# untitled.net
KiCad netlist of a schematic drawn in EAGLE
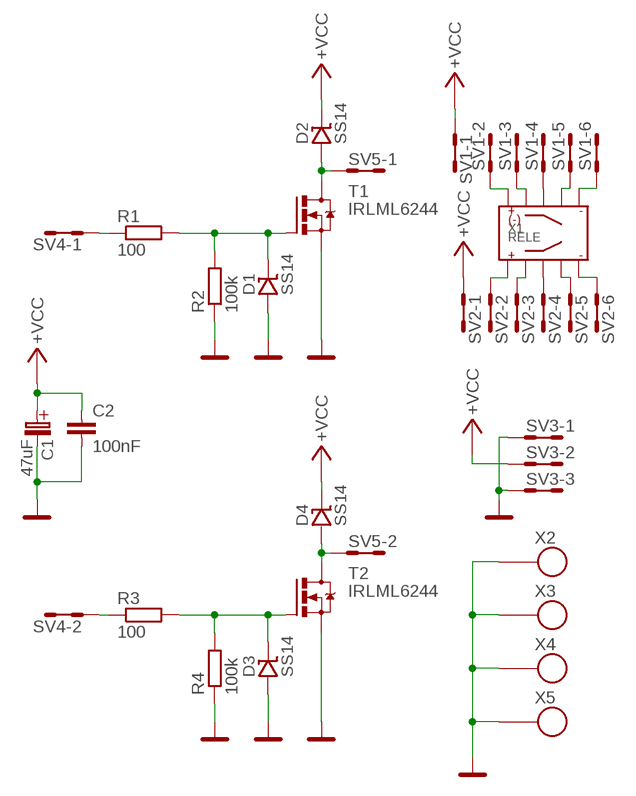
[diagram p0: schematic, sheet 1]

(export (version "E")
  (design (tool "Eeschema 10.0.6"))
  (components
    (comp (ref "C1") (value "47uF") (footprint "eagle-import:B") (libsource (lib "eagle-import") (part "B")))
    (comp (ref "C2")
      (value "100nF")
      (footprint "eagle-import:C0805")
      (libsource (lib "eagle-import") (part "C0805"))
    )
    (comp (ref "D1")
      (value "SS14")
      (footprint "eagle-import:SMA")
      (libsource (lib "eagle-import") (part "D-SHOTKY-SMA"))
    )
    (comp (ref "D2")
      (value "SS14")
      (footprint "eagle-import:SMA")
      (libsource (lib "eagle-import") (part "D-SHOTKY-SMA"))
    )
    (comp (ref "D3")
      (value "SS14")
      (footprint "eagle-import:SMA")
      (libsource (lib "eagle-import") (part "D-SHOTKY-SMA"))
    )
    (comp (ref "D4")
      (value "SS14")
      (footprint "eagle-import:SMA")
      (libsource (lib "eagle-import") (part "D-SHOTKY-SMA"))
    )
    (comp (ref "R1")
      (value "100")
      (footprint "eagle-import:0805")
      (libsource (lib "eagle-import") (part "R0805"))
    )
    (comp (ref "R2")
      (value "100k")
      (footprint "eagle-import:0805")
      (libsource (lib "eagle-import") (part "R0805"))
    )
    (comp (ref "R3")
      (value "100")
      (footprint "eagle-import:0805")
      (libsource (lib "eagle-import") (part "R0805"))
    )
    (comp (ref "R4")
      (value "100k")
      (footprint "eagle-import:0805")
      (libsource (lib "eagle-import") (part "R0805"))
    )
    (comp (ref "SV1")
      (value "MA06-2")
      (footprint "eagle-import:MA06-2")
      (libsource (lib "eagle-import") (part "MA06-2"))
    )
    (comp (ref "SV2")
      (value "MA06-2")
      (footprint "eagle-import:MA06-2")
      (libsource (lib "eagle-import") (part "MA06-2"))
    )
    (comp (ref "SV3")
      (value "MA03-2")
      (footprint "eagle-import:MA03-2")
      (libsource (lib "eagle-import") (part "MA03-2"))
    )
    (comp (ref "SV4")
      (value "MA02-2")
      (footprint "eagle-import:MA02-2")
      (libsource (lib "eagle-import") (part "MA02-2"))
    )
    (comp (ref "SV5")
      (value "MA02-2")
      (footprint "eagle-import:MA02-2")
      (libsource (lib "eagle-import") (part "MA02-2"))
    )
    (comp (ref "T1")
      (value "IRLML6244")
      (footprint "eagle-import:SOT23")
      (libsource (lib "eagle-import") (part "IRLML6244TRPBF"))
    )
    (comp (ref "T2")
      (value "IRLML6244")
      (footprint "eagle-import:SOT23")
      (libsource (lib "eagle-import") (part "IRLML6244TRPBF"))
    )
    (comp (ref "X1")
      (value "RELE")
      (footprint "eagle-import:RELE")
      (libsource (lib "eagle-import") (part "RELE"))
    )
    (comp (ref "X2")
      (value "SROUB3M")
      (footprint "eagle-import:SROUB3M")
      (libsource (lib "eagle-import") (part "SROUB3M"))
    )
    (comp (ref "X3")
      (value "SROUB3M")
      (footprint "eagle-import:SROUB3M")
      (libsource (lib "eagle-import") (part "SROUB3M"))
    )
    (comp (ref "X4")
      (value "SROUB3M")
      (footprint "eagle-import:SROUB3M")
      (libsource (lib "eagle-import") (part "SROUB3M"))
    )
    (comp (ref "X5")
      (value "SROUB3M")
      (footprint "eagle-import:SROUB3M")
      (libsource (lib "eagle-import") (part "SROUB3M"))
    )
  )
  (nets
    (net (code "1") (name "+VCC") (class "Default")
      (node (ref "C1") (pin "+") (pinfunction "C_EL+_+") (pintype "passive"))
      (node (ref "C2") (pin "1") (pinfunction "1_1") (pintype "passive"))
      (node (ref "D2") (pin "K") (pinfunction "K_K") (pintype "passive"))
      (node (ref "D4") (pin "K") (pinfunction "K_K") (pintype "passive"))
      (node (ref "SV1") (pin "1") (pinfunction "K_1") (pintype "passive"))
      (node (ref "SV1") (pin "2") (pinfunction "K_2") (pintype "passive"))
      (node (ref "SV2") (pin "1") (pinfunction "K_1") (pintype "passive"))
      (node (ref "SV2") (pin "2") (pinfunction "K_2") (pintype "passive"))
      (node (ref "SV3") (pin "3") (pinfunction "K_3") (pintype "passive"))
      (node (ref "SV3") (pin "4") (pinfunction "K_4") (pintype "passive"))
    )
    (net (code "2") (name "GND") (class "Default")
      (node (ref "C1") (pin "-") (pinfunction "C_EL-_-") (pintype "passive"))
      (node (ref "C2") (pin "2") (pinfunction "2_2") (pintype "passive"))
      (node (ref "D1") (pin "A") (pinfunction "A_A") (pintype "passive"))
      (node (ref "D3") (pin "A") (pinfunction "A_A") (pintype "passive"))
      (node (ref "R2") (pin "1") (pinfunction "1_1") (pintype "passive"))
      (node (ref "R4") (pin "1") (pinfunction "1_1") (pintype "passive"))
      (node (ref "SV3") (pin "1") (pinfunction "K_1") (pintype "passive"))
      (node (ref "SV3") (pin "2") (pinfunction "K_2") (pintype "passive"))
      (node (ref "SV3") (pin "5") (pinfunction "K_5") (pintype "passive"))
      (node (ref "SV3") (pin "6") (pinfunction "K_6") (pintype "passive"))
      (node (ref "T1") (pin "2") (pinfunction "S_2") (pintype "passive"))
      (node (ref "T2") (pin "2") (pinfunction "S_2") (pintype "passive"))
      (node (ref "X2") (pin "P$1") (pinfunction "P$1_P$1") (pintype "bidirectional"))
      (node (ref "X3") (pin "P$1") (pinfunction "P$1_P$1") (pintype "bidirectional"))
      (node (ref "X4") (pin "P$1") (pinfunction "P$1_P$1") (pintype "bidirectional"))
      (node (ref "X5") (pin "P$1") (pinfunction "P$1_P$1") (pintype "bidirectional"))
    )
    (net (code "3") (name "Net-(R1-Pad1)") (class "Default")
      (node (ref "R1") (pin "1") (pinfunction "1_1") (pintype "passive"))
      (node (ref "SV4") (pin "1") (pinfunction "K_1") (pintype "passive"))
      (node (ref "SV4") (pin "2") (pinfunction "K_2") (pintype "passive"))
    )
    (net (code "4") (name "Net-(R3-Pad1)") (class "Default")
      (node (ref "R3") (pin "1") (pinfunction "1_1") (pintype "passive"))
      (node (ref "SV4") (pin "3") (pinfunction "K_3") (pintype "passive"))
      (node (ref "SV4") (pin "4") (pinfunction "K_4") (pintype "passive"))
    )
    (net (code "5") (name "Net-(T1-D)") (class "Default")
      (node (ref "D2") (pin "A") (pinfunction "A_A") (pintype "passive"))
      (node (ref "SV5") (pin "1") (pinfunction "K_1") (pintype "passive"))
      (node (ref "SV5") (pin "2") (pinfunction "K_2") (pintype "passive"))
      (node (ref "T1") (pin "3") (pinfunction "D_3") (pintype "passive"))
    )
    (net (code "6") (name "Net-(T1-G)") (class "Default")
      (node (ref "D1") (pin "K") (pinfunction "K_K") (pintype "passive"))
      (node (ref "R1") (pin "2") (pinfunction "2_2") (pintype "passive"))
      (node (ref "R2") (pin "2") (pinfunction "2_2") (pintype "passive"))
      (node (ref "T1") (pin "1") (pinfunction "G_1") (pintype "passive"))
    )
    (net (code "7") (name "Net-(T2-D)") (class "Default")
      (node (ref "D4") (pin "A") (pinfunction "A_A") (pintype "passive"))
      (node (ref "SV5") (pin "3") (pinfunction "K_3") (pintype "passive"))
      (node (ref "SV5") (pin "4") (pinfunction "K_4") (pintype "passive"))
      (node (ref "T2") (pin "3") (pinfunction "D_3") (pintype "passive"))
    )
    (net (code "8") (name "Net-(T2-G)") (class "Default")
      (node (ref "D3") (pin "K") (pinfunction "K_K") (pintype "passive"))
      (node (ref "R3") (pin "2") (pinfunction "2_2") (pintype "passive"))
      (node (ref "R4") (pin "2") (pinfunction "2_2") (pintype "passive"))
      (node (ref "T2") (pin "1") (pinfunction "G_1") (pintype "passive"))
    )
    (net (code "9") (name "Net-(X1-P$1)") (class "Default")
      (node (ref "SV2") (pin "3") (pinfunction "K_3") (pintype "passive"))
      (node (ref "SV2") (pin "4") (pinfunction "K_4") (pintype "passive"))
      (node (ref "X1") (pin "1") (pinfunction "P$1_1") (pintype "passive"))
    )
    (net (code "10") (name "Net-(X1-P$2)") (class "Default")
      (node (ref "SV2") (pin "5") (pinfunction "K_5") (pintype "passive"))
      (node (ref "SV2") (pin "6") (pinfunction "K_6") (pintype "passive"))
      (node (ref "X1") (pin "2") (pinfunction "P$2_2") (pintype "passive"))
    )
    (net (code "11") (name "Net-(X1-P$3)") (class "Default")
      (node (ref "SV2") (pin "7") (pinfunction "K_7") (pintype "passive"))
      (node (ref "SV2") (pin "8") (pinfunction "K_8") (pintype "passive"))
      (node (ref "X1") (pin "3") (pinfunction "P$3_3") (pintype "passive"))
    )
    (net (code "12") (name "Net-(X1-P$4)") (class "Default")
      (node (ref "SV2") (pin "10") (pinfunction "K_10") (pintype "passive"))
      (node (ref "SV2") (pin "9") (pinfunction "K_9") (pintype "passive"))
      (node (ref "X1") (pin "4") (pinfunction "P$4_4") (pintype "passive"))
    )
    (net (code "13") (name "Net-(X1-P$5)") (class "Default")
      (node (ref "SV2") (pin "11") (pinfunction "K_11") (pintype "passive"))
      (node (ref "SV2") (pin "12") (pinfunction "K_12") (pintype "passive"))
      (node (ref "X1") (pin "5") (pinfunction "P$5_5") (pintype "passive"))
    )
    (net (code "14") (name "Net-(X1-P$6)") (class "Default")
      (node (ref "SV1") (pin "11") (pinfunction "K_11") (pintype "passive"))
      (node (ref "SV1") (pin "12") (pinfunction "K_12") (pintype "passive"))
      (node (ref "X1") (pin "6") (pinfunction "P$6_6") (pintype "passive"))
    )
    (net (code "15") (name "Net-(X1-P$7)") (class "Default")
      (node (ref "SV1") (pin "10") (pinfunction "K_10") (pintype "passive"))
      (node (ref "SV1") (pin "9") (pinfunction "K_9") (pintype "passive"))
      (node (ref "X1") (pin "7") (pinfunction "P$7_7") (pintype "passive"))
    )
    (net (code "16") (name "Net-(X1-P$8)") (class "Default")
      (node (ref "SV1") (pin "7") (pinfunction "K_7") (pintype "passive"))
      (node (ref "SV1") (pin "8") (pinfunction "K_8") (pintype "passive"))
      (node (ref "X1") (pin "8") (pinfunction "P$8_8") (pintype "passive"))
    )
    (net (code "17") (name "Net-(X1-P$9)") (class "Default")
      (node (ref "SV1") (pin "5") (pinfunction "K_5") (pintype "passive"))
      (node (ref "SV1") (pin "6") (pinfunction "K_6") (pintype "passive"))
      (node (ref "X1") (pin "9") (pinfunction "P$9_9") (pintype "passive"))
    )
    (net (code "18") (name "Net-(X1-P$10)") (class "Default")
      (node (ref "SV1") (pin "3") (pinfunction "K_3") (pintype "passive"))
      (node (ref "SV1") (pin "4") (pinfunction "K_4") (pintype "passive"))
      (node (ref "X1") (pin "10") (pinfunction "P$10_10") (pintype "passive"))
    )
  )
)
